# 14_-MAIN_CONNECTORS.net
KiCad netlist of a schematic drawn in Altium Designer
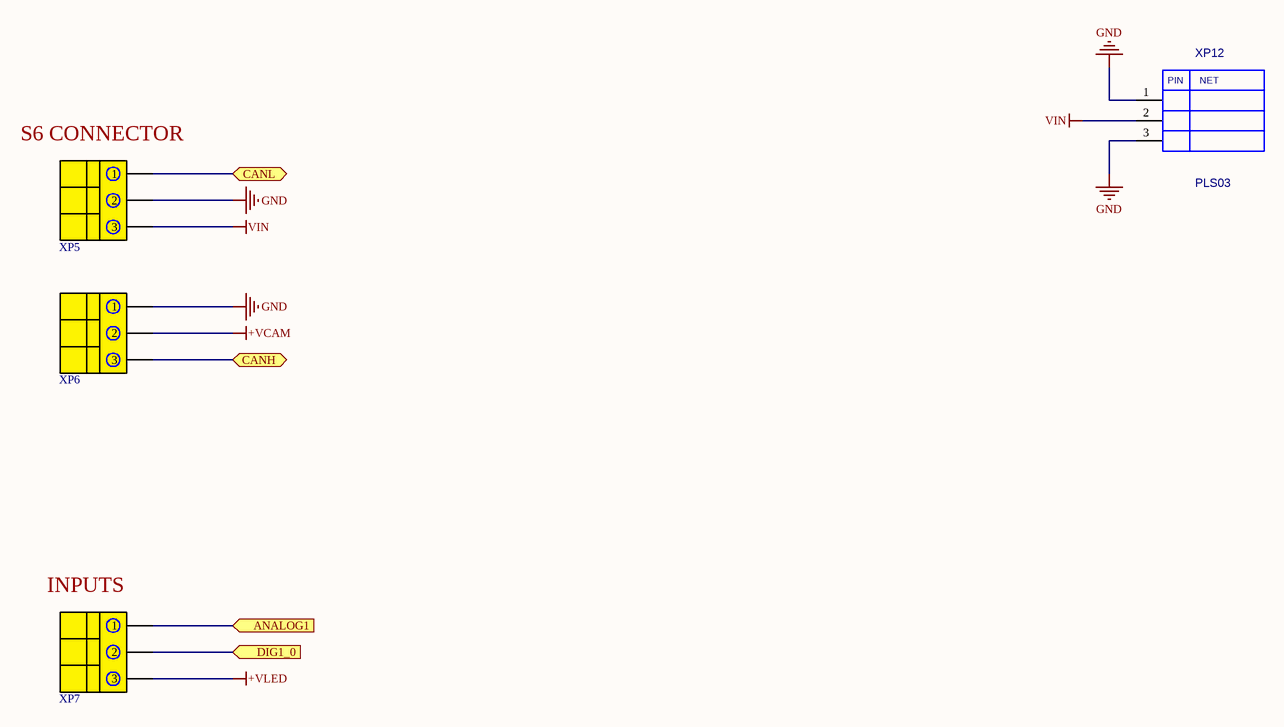
[diagram p0: [14]-MAIN_CONNECTORS.SchDoc]

(export (version "E")
  (design (tool "Eeschema 10.0.6"))
  (components
    (comp (ref "XP5")
      (value "DG330-3PIN")
      (footprint "DG330-3P")
      (description "Degson 3 pin connector rear")
      (libsource (lib "fizik_lib") (part "DG330-3P"))
    )
    (comp (ref "XP6")
      (value "DG330-3PIN")
      (footprint "DG330-3P")
      (description "Degson 3 pin connector rear")
      (libsource (lib "fizik_lib") (part "DG330-3P"))
    )
    (comp (ref "XP7")
      (value "DG330-3PIN")
      (footprint "DG330-3P")
      (description "Degson 3 pin connector rear")
      (libsource (lib "fizik_lib") (part "DG330-3P"))
    )
    (comp (ref "XP12") (value "PLS03") (footprint "PLS-03") (libsource (lib "fizik_lib") (part "PLS03")))
  )
  (nets
    (net (code "1") (name "+VCAM") (class "Default")
      (node (ref "XP6") (pin "2") (pinfunction "2_2") (pintype "passive"))
    )
    (net (code "2") (name "+VLED") (class "Default")
      (node (ref "XP7") (pin "3") (pinfunction "3_3") (pintype "passive"))
    )
    (net (code "3") (name "/ANALOG1") (class "Default")
      (node (ref "XP7") (pin "1") (pinfunction "1_1") (pintype "passive"))
    )
    (net (code "4") (name "/CANH") (class "Default")
      (node (ref "XP6") (pin "3") (pinfunction "3_3") (pintype "passive"))
    )
    (net (code "5") (name "/CANL") (class "Default")
      (node (ref "XP5") (pin "1") (pinfunction "1_1") (pintype "passive"))
    )
    (net (code "6") (name "/DIG1_0") (class "Default")
      (node (ref "XP7") (pin "2") (pinfunction "2_2") (pintype "passive"))
    )
    (net (code "7") (name "GND") (class "Default")
      (node (ref "XP12") (pin "1") (pinfunction "1_1") (pintype "passive"))
      (node (ref "XP12") (pin "3") (pinfunction "3_3") (pintype "passive"))
      (node (ref "XP5") (pin "2") (pinfunction "2_2") (pintype "passive"))
      (node (ref "XP6") (pin "1") (pinfunction "1_1") (pintype "passive"))
    )
    (net (code "8") (name "VIN") (class "Default")
      (node (ref "XP12") (pin "2") (pinfunction "2_2") (pintype "passive"))
      (node (ref "XP5") (pin "3") (pinfunction "3_3") (pintype "passive"))
    )
  )
)
